# uC.net
KiCad netlist of a schematic drawn in Altium Designer
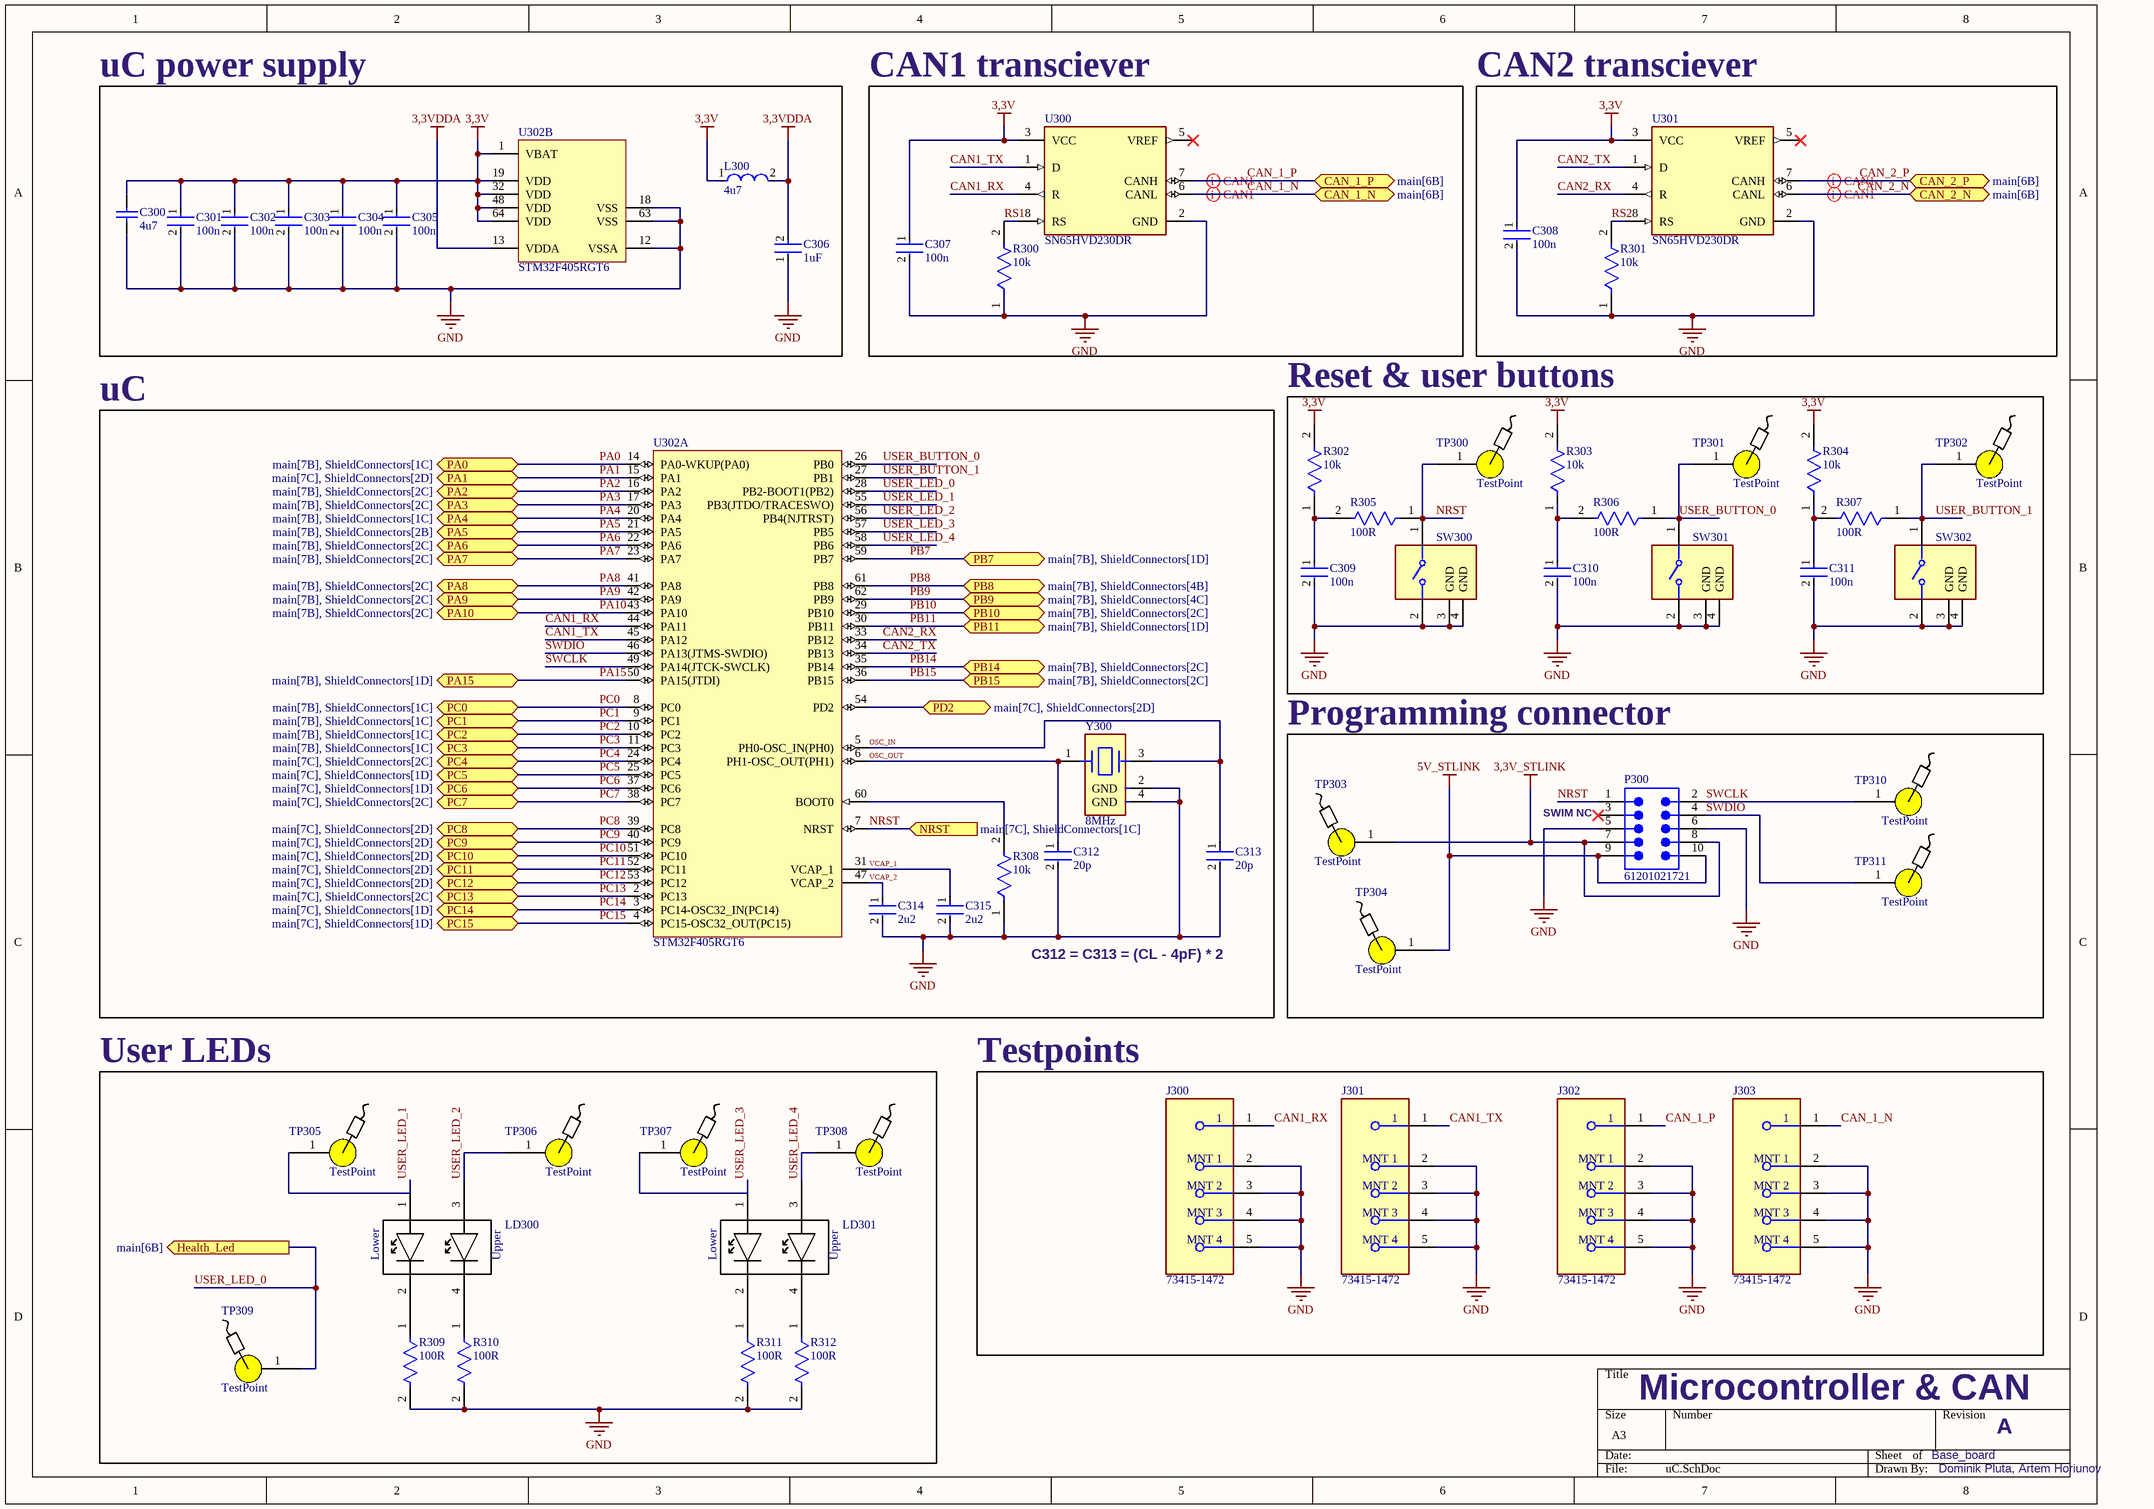
[diagram p0: uC.SchDoc]

(export (version "E")
  (design (tool "Eeschema 10.0.6"))
  (components
    (comp (ref "C300")
      (value "4u7")
      (footprint "CAPC1608X87X35NL15T15")
      (fields (field (name "PART NUMBER") "C0603C475K8PACTU") (field (name "MANUFACTURER") "Kemet"))
      (libsource (lib "Altium Content Vault") (part "CAP"))
    )
    (comp (ref "C301")
      (value "100n")
      (footprint "FP-C0603C-CF-MFG")
      (description "CAP CER 0.1UF 50V X7R 0603")
      (fields (field (name "TOLERANCE") "0.1") (field (name "MANUFACTURER") "KEMET"))
      (libsource (lib "Altium Content Vault") (part "b4654b650e69147ec39a6b967a45e02"))
    )
    (comp (ref "C302")
      (value "100n")
      (footprint "FP-C0603C-CF-MFG")
      (description "CAP CER 0.1UF 50V X7R 0603")
      (fields (field (name "TOLERANCE") "0.1") (field (name "MANUFACTURER") "KEMET"))
      (libsource (lib "Altium Content Vault") (part "b4654b650e69147ec39a6b967a45e02"))
    )
    (comp (ref "C303")
      (value "100n")
      (footprint "FP-C0603C-CF-MFG")
      (description "CAP CER 0.1UF 50V X7R 0603")
      (fields (field (name "TOLERANCE") "0.1") (field (name "MANUFACTURER") "KEMET"))
      (libsource (lib "Altium Content Vault") (part "b4654b650e69147ec39a6b967a45e02"))
    )
    (comp (ref "C304")
      (value "100n")
      (footprint "FP-C0603C-CF-MFG")
      (description "CAP CER 0.1UF 50V X7R 0603")
      (fields (field (name "TOLERANCE") "0.1") (field (name "MANUFACTURER") "KEMET"))
      (libsource (lib "Altium Content Vault") (part "b4654b650e69147ec39a6b967a45e02"))
    )
    (comp (ref "C305")
      (value "100n")
      (footprint "FP-C0603C-CF-MFG")
      (description "CAP CER 0.1UF 50V X7R 0603")
      (fields (field (name "TOLERANCE") "0.1") (field (name "MANUFACTURER") "KEMET"))
      (libsource (lib "Altium Content Vault") (part "b4654b650e69147ec39a6b967a45e02"))
    )
    (comp (ref "C306")
      (value "1uF")
      (footprint "FP-C1608-080-0_1-IPC_B")
      (description "Multilayer Ceramic Capacitors 1μF ±10% 50V X5R SMD 0603")
      (fields (field (name "VOLTAGE") "50V") (field (name "TOLERANCE") "10%"))
      (libsource (lib "Altium Content Vault") (part "236180d848d6139a670b325ea6854c9"))
    )
    (comp (ref "C307")
      (value "100n")
      (footprint "FP-C0603C-CF-MFG")
      (description "CAP CER 0.1UF 50V X7R 0603")
      (fields (field (name "TOLERANCE") "0.1") (field (name "MANUFACTURER") "KEMET"))
      (libsource (lib "Altium Content Vault") (part "b4654b650e69147ec39a6b967a45e02"))
    )
    (comp (ref "C308")
      (value "100n")
      (footprint "FP-C0603C-CF-MFG")
      (description "CAP CER 0.1UF 50V X7R 0603")
      (fields (field (name "TOLERANCE") "0.1") (field (name "MANUFACTURER") "KEMET"))
      (libsource (lib "Altium Content Vault") (part "b4654b650e69147ec39a6b967a45e02"))
    )
    (comp (ref "C309")
      (value "100n")
      (footprint "FP-C0603C-CF-MFG")
      (description "CAP CER 0.1UF 50V X7R 0603")
      (fields (field (name "TOLERANCE") "0.1") (field (name "MANUFACTURER") "KEMET"))
      (libsource (lib "Altium Content Vault") (part "b4654b650e69147ec39a6b967a45e02"))
    )
    (comp (ref "C310")
      (value "100n")
      (footprint "FP-C0603C-CF-MFG")
      (description "CAP CER 0.1UF 50V X7R 0603")
      (fields (field (name "TOLERANCE") "0.1") (field (name "MANUFACTURER") "KEMET"))
      (libsource (lib "Altium Content Vault") (part "b4654b650e69147ec39a6b967a45e02"))
    )
    (comp (ref "C311")
      (value "100n")
      (footprint "FP-C0603C-CF-MFG")
      (description "CAP CER 0.1UF 50V X7R 0603")
      (fields (field (name "TOLERANCE") "0.1") (field (name "MANUFACTURER") "KEMET"))
      (libsource (lib "Altium Content Vault") (part "b4654b650e69147ec39a6b967a45e02"))
    )
    (comp (ref "C312")
      (value "20p")
      (footprint "FP-C0603C-CF-MFG")
      (description "CAP CER 20PF 50V 5% NP0 0603")
      (fields
        (field (name "MANUFACTURER PART NUMBER") "C0603C200J5GACTU")
        (field (name "MANUFACTURER") "KEMET")
      )
      (libsource (lib "Altium Content Vault") (part "b4654b650e69147ec39a6b967a45e02"))
    )
    (comp (ref "C313")
      (value "20p")
      (footprint "FP-C0603C-CF-MFG")
      (description "CAP CER 20PF 50V 5% NP0 0603")
      (fields
        (field (name "MANUFACTURER PART NUMBER") "C0603C200J5GACTU")
        (field (name "MANUFACTURER") "KEMET")
      )
      (libsource (lib "Altium Content Vault") (part "b4654b650e69147ec39a6b967a45e02"))
    )
    (comp (ref "C314")
      (value "2u2")
      (footprint "FP-GRM188-0_1-e0_2_0_5-MFG")
      (description "Chip Multilayer Ceramic Capacitors for General Purpose, 0603, 2.2uF, X7R, 15%, 10%, 10V")
      (fields (field (name "VOLTAGE") "10V") (field (name "TOLERANCE") "10%"))
      (libsource (lib "Altium Content Vault") (part "11868f565c42a9108669ba33697ecf6"))
    )
    (comp (ref "C315")
      (value "2u2")
      (footprint "FP-GRM188-0_1-e0_2_0_5-MFG")
      (description "Chip Multilayer Ceramic Capacitors for General Purpose, 0603, 2.2uF, X7R, 15%, 10%, 10V")
      (fields (field (name "VOLTAGE") "10V") (field (name "TOLERANCE") "10%"))
      (libsource (lib "Altium Content Vault") (part "11868f565c42a9108669ba33697ecf6"))
    )
    (comp (ref "J300")
      (value "73415-1472")
      (footprint "FP-73415-1472-MFG")
      (libsource (lib "Altium Content Vault") (part "c65b8a639cdaef1819ea20b5466f8fa"))
    )
    (comp (ref "J301")
      (value "73415-1472")
      (footprint "FP-73415-1472-MFG")
      (libsource (lib "Altium Content Vault") (part "c65b8a639cdaef1819ea20b5466f8fa"))
    )
    (comp (ref "J302")
      (value "73415-1472")
      (footprint "FP-73415-1472-MFG")
      (libsource (lib "Altium Content Vault") (part "c65b8a639cdaef1819ea20b5466f8fa"))
    )
    (comp (ref "J303")
      (value "73415-1472")
      (footprint "FP-73415-1472-MFG")
      (libsource (lib "Altium Content Vault") (part "c65b8a639cdaef1819ea20b5466f8fa"))
    )
    (comp (ref "L300")
      (value "4u7")
      (footprint "FP-LQM21DH_70-IPC_C")
      (description "Multilayer Type Inductor for General Circuits, 0805 (2012), 22μH, 30%, 0.65Ω, 13mA")
      (fields (field (name "TOLERANCE") "10%"))
      (libsource (lib "Altium Content Vault") (part "725321dda6339637d4d059423bc1c3c"))
    )
    (comp (ref "LD300")
      (value "~")
      (footprint "LedHolder:LED_HOLDER")
      (libsource (lib "LedHolder") (part "DoubleStack_Side_Led_3mm"))
    )
    (comp (ref "LD301")
      (value "~")
      (footprint "LedHolder:LED_HOLDER")
      (libsource (lib "LedHolder") (part "DoubleStack_Side_Led_3mm"))
    )
    (comp (ref "P300")
      (value "61201021721")
      (footprint "61201021721")
      (libsource (lib "Altium Content Vault") (part "Header_Male_2R_10P"))
    )
    (comp (ref "R300")
      (value "10k")
      (footprint "FP-RC0603-0_55-IPC_C")
      (description "RES 10K OHM 1% 1/10W 0603")
      (fields (field (name "TOLERANCE") "1%"))
      (libsource (lib "Altium Content Vault") (part "1029c3af85768c4190bb7ad29bc67b5"))
    )
    (comp (ref "R301")
      (value "10k")
      (footprint "FP-RC0603-0_55-IPC_C")
      (description "RES 10K OHM 1% 1/10W 0603")
      (fields (field (name "TOLERANCE") "1%"))
      (libsource (lib "Altium Content Vault") (part "1029c3af85768c4190bb7ad29bc67b5"))
    )
    (comp (ref "R302")
      (value "10k")
      (footprint "FP-RC0603-0_55-IPC_C")
      (description "RES 10K OHM 1% 1/10W 0603")
      (fields (field (name "TOLERANCE") "1%"))
      (libsource (lib "Altium Content Vault") (part "1029c3af85768c4190bb7ad29bc67b5"))
    )
    (comp (ref "R303")
      (value "10k")
      (footprint "FP-RC0603-0_55-IPC_C")
      (description "RES 10K OHM 1% 1/10W 0603")
      (fields (field (name "TOLERANCE") "1%"))
      (libsource (lib "Altium Content Vault") (part "1029c3af85768c4190bb7ad29bc67b5"))
    )
    (comp (ref "R304")
      (value "10k")
      (footprint "FP-RC0603-0_55-IPC_C")
      (description "RES 10K OHM 1% 1/10W 0603")
      (fields (field (name "TOLERANCE") "1%"))
      (libsource (lib "Altium Content Vault") (part "1029c3af85768c4190bb7ad29bc67b5"))
    )
    (comp (ref "R305")
      (value "100R")
      (footprint "FP-RC0603-0_55-MFG")
      (fields (field (name "TOLERANCE") "1%"))
      (libsource (lib "Altium Content Vault") (part "1029c3af85768c4190bb7ad29bc67b5"))
    )
    (comp (ref "R306")
      (value "100R")
      (footprint "FP-RC0603-0_55-MFG")
      (fields (field (name "TOLERANCE") "1%"))
      (libsource (lib "Altium Content Vault") (part "1029c3af85768c4190bb7ad29bc67b5"))
    )
    (comp (ref "R307")
      (value "100R")
      (footprint "FP-RC0603-0_55-MFG")
      (fields (field (name "TOLERANCE") "1%"))
      (libsource (lib "Altium Content Vault") (part "1029c3af85768c4190bb7ad29bc67b5"))
    )
    (comp (ref "R308")
      (value "10k")
      (footprint "FP-RC0603-0_55-IPC_C")
      (description "RES 10K OHM 1% 1/10W 0603")
      (fields (field (name "TOLERANCE") "1%"))
      (libsource (lib "Altium Content Vault") (part "1029c3af85768c4190bb7ad29bc67b5"))
    )
    (comp (ref "R309")
      (value "100R")
      (footprint "FP-RC0603-0_55-MFG")
      (fields (field (name "TOLERANCE") "1%"))
      (libsource (lib "Altium Content Vault") (part "1029c3af85768c4190bb7ad29bc67b5"))
    )
    (comp (ref "R310")
      (value "100R")
      (footprint "FP-RC0603-0_55-MFG")
      (fields (field (name "TOLERANCE") "1%"))
      (libsource (lib "Altium Content Vault") (part "1029c3af85768c4190bb7ad29bc67b5"))
    )
    (comp (ref "R311")
      (value "100R")
      (footprint "FP-RC0603-0_55-MFG")
      (fields (field (name "TOLERANCE") "1%"))
      (libsource (lib "Altium Content Vault") (part "1029c3af85768c4190bb7ad29bc67b5"))
    )
    (comp (ref "R312")
      (value "100R")
      (footprint "FP-RC0603-0_55-MFG")
      (fields (field (name "TOLERANCE") "1%"))
      (libsource (lib "Altium Content Vault") (part "1029c3af85768c4190bb7ad29bc67b5"))
    )
    (comp (ref "SW300")
      (value "B3F-3122")
      (footprint "FP-B3F-3122-MFG")
      (description "SWITCH TACTILE SPST-NO 0.05A 24V")
      (libsource (lib "Altium Content Vault") (part "05c531d4b500f7e9514fa3f65f375ae"))
    )
    (comp (ref "SW301")
      (value "B3F-3122")
      (footprint "FP-B3F-3122-MFG")
      (description "SWITCH TACTILE SPST-NO 0.05A 24V")
      (libsource (lib "Altium Content Vault") (part "05c531d4b500f7e9514fa3f65f375ae"))
    )
    (comp (ref "SW302")
      (value "B3F-3122")
      (footprint "FP-B3F-3122-MFG")
      (description "SWITCH TACTILE SPST-NO 0.05A 24V")
      (libsource (lib "Altium Content Vault") (part "05c531d4b500f7e9514fa3f65f375ae"))
    )
    (comp (ref "TP300")
      (value "TestPoint")
      (footprint "TestPoint")
      (libsource (lib "TestPoint") (part "TestPoint"))
    )
    (comp (ref "TP301")
      (value "TestPoint")
      (footprint "TestPoint")
      (libsource (lib "TestPoint") (part "TestPoint"))
    )
    (comp (ref "TP302")
      (value "TestPoint")
      (footprint "TestPoint")
      (libsource (lib "TestPoint") (part "TestPoint"))
    )
    (comp (ref "TP303")
      (value "TestPoint")
      (footprint "TestPoint")
      (libsource (lib "TestPoint") (part "TestPoint"))
    )
    (comp (ref "TP304")
      (value "TestPoint")
      (footprint "TestPoint")
      (libsource (lib "TestPoint") (part "TestPoint"))
    )
    (comp (ref "TP305")
      (value "TestPoint")
      (footprint "TestPoint")
      (libsource (lib "TestPoint") (part "TestPoint"))
    )
    (comp (ref "TP306")
      (value "TestPoint")
      (footprint "TestPoint")
      (libsource (lib "TestPoint") (part "TestPoint"))
    )
    (comp (ref "TP307")
      (value "TestPoint")
      (footprint "TestPoint")
      (libsource (lib "TestPoint") (part "TestPoint"))
    )
    (comp (ref "TP308")
      (value "TestPoint")
      (footprint "TestPoint")
      (libsource (lib "TestPoint") (part "TestPoint"))
    )
    (comp (ref "TP309")
      (value "TestPoint")
      (footprint "TestPoint")
      (libsource (lib "TestPoint") (part "TestPoint"))
    )
    (comp (ref "TP310")
      (value "TestPoint")
      (footprint "TestPoint")
      (libsource (lib "TestPoint") (part "TestPoint"))
    )
    (comp (ref "TP311")
      (value "TestPoint")
      (footprint "TestPoint")
      (libsource (lib "TestPoint") (part "TestPoint"))
    )
    (comp (ref "U300")
      (value "SN65HVD230DR")
      (footprint "FP-D0008A-IPC_A")
      (description "IC TRANSCEIVER HALF 1/1 8SOIC")
      (libsource (lib "Altium Content Vault") (part "43b56812b1adf0e60a7acfb7c27ab91"))
    )
    (comp (ref "U301")
      (value "SN65HVD230DR")
      (footprint "FP-D0008A-IPC_A")
      (description "IC TRANSCEIVER HALF 1/1 8SOIC")
      (libsource (lib "Altium Content Vault") (part "43b56812b1adf0e60a7acfb7c27ab91"))
    )
    (comp (ref "U302")
      (value "STM32F405RGT6")
      (footprint "STM-LQFP64_M")
      (fields (field (name "MANUFACTURER") "STMicroelectronics"))
      (libsource (lib "Altium Content Vault") (part "MC-ARM-STM32F4X5-SQ64"))
    )
    (comp (ref "Y300")
      (value "8MHz")
      (footprint "FP-7M-MFG")
      (description "Crystal")
      (fields (field (name "TOLERANCE") "10ppm"))
      (libsource (lib "Altium Content Vault") (part "41079aabb0e87794b56622915be14ed"))
    )
  )
  (nets
    (net (code "2") (name "/CAN1_RX") (class "Default")
      (node (ref "J300") (pin "1") (pinfunction "1_1") (pintype "passive"))
      (node (ref "U300") (pin "4") (pinfunction "R_4") (pintype "output"))
      (node (ref "U302") (pin "44") (pinfunction "PA11_44") (pintype "bidirectional"))
    )
    (net (code "3") (name "/CAN1_TX") (class "Default")
      (node (ref "J301") (pin "1") (pinfunction "1_1") (pintype "passive"))
      (node (ref "U300") (pin "1") (pinfunction "D_1") (pintype "input"))
      (node (ref "U302") (pin "45") (pinfunction "PA12_45") (pintype "bidirectional"))
    )
    (net (code "4") (name "/CAN2_RX") (class "Default")
      (node (ref "U301") (pin "4") (pinfunction "R_4") (pintype "output"))
      (node (ref "U302") (pin "33") (pinfunction "PB12_33") (pintype "bidirectional"))
    )
    (net (code "5") (name "/CAN2_TX") (class "Default")
      (node (ref "U301") (pin "1") (pinfunction "D_1") (pintype "input"))
      (node (ref "U302") (pin "34") (pinfunction "PB13_34") (pintype "bidirectional"))
    )
    (net (code "6") (name "/CAN_1_N") (class "Default")
      (node (ref "J303") (pin "1") (pinfunction "1_1") (pintype "passive"))
      (node (ref "U300") (pin "6") (pinfunction "CANL_6") (pintype "bidirectional"))
    )
    (net (code "7") (name "/CAN_1_P") (class "Default")
      (node (ref "J302") (pin "1") (pinfunction "1_1") (pintype "passive"))
      (node (ref "U300") (pin "7") (pinfunction "CANH_7") (pintype "bidirectional"))
    )
    (net (code "8") (name "/CAN_2_N") (class "Default")
      (node (ref "U301") (pin "6") (pinfunction "CANL_6") (pintype "bidirectional"))
    )
    (net (code "9") (name "/CAN_2_P") (class "Default")
      (node (ref "U301") (pin "7") (pinfunction "CANH_7") (pintype "bidirectional"))
    )
    (net (code "10") (name "/NRST") (class "Default")
      (node (ref "P300") (pin "1") (pinfunction "1_1") (pintype "passive"))
      (node (ref "R305") (pin "1") (pinfunction "1_1") (pintype "passive"))
      (node (ref "SW300") (pin "1") (pinfunction "1_1") (pintype "passive"))
      (node (ref "TP300") (pin "1") (pintype "passive"))
      (node (ref "U302") (pin "7") (pinfunction "NRST_7") (pintype "bidirectional"))
    )
    (net (code "11") (name "/OSC_IN") (class "Default")
      (node (ref "C313") (pin "1") (pinfunction "1_1") (pintype "passive"))
      (node (ref "U302") (pin "5") (pinfunction "PH0-OSC_IN(PH0)_5") (pintype "bidirectional"))
      (node (ref "Y300") (pin "3") (pinfunction "3_3") (pintype "passive"))
    )
    (net (code "12") (name "/OSC_OUT") (class "Default")
      (node (ref "C312") (pin "1") (pinfunction "1_1") (pintype "passive"))
      (node (ref "U302") (pin "6") (pinfunction "PH1-OSC_OUT(PH1)_6") (pintype "bidirectional"))
      (node (ref "Y300") (pin "1") (pinfunction "1_1") (pintype "passive"))
    )
    (net (code "13") (name "/PA0") (class "Default")
      (node (ref "U302") (pin "14") (pinfunction "PA0-WKUP(PA0)_14") (pintype "bidirectional"))
    )
    (net (code "14") (name "/PA1") (class "Default")
      (node (ref "U302") (pin "15") (pinfunction "PA1_15") (pintype "bidirectional"))
    )
    (net (code "15") (name "/PA2") (class "Default")
      (node (ref "U302") (pin "16") (pinfunction "PA2_16") (pintype "bidirectional"))
    )
    (net (code "16") (name "/PA3") (class "Default")
      (node (ref "U302") (pin "17") (pinfunction "PA3_17") (pintype "bidirectional"))
    )
    (net (code "17") (name "/PA4") (class "Default")
      (node (ref "U302") (pin "20") (pinfunction "PA4_20") (pintype "bidirectional"))
    )
    (net (code "18") (name "/PA5") (class "Default")
      (node (ref "U302") (pin "21") (pinfunction "PA5_21") (pintype "bidirectional"))
    )
    (net (code "19") (name "/PA6") (class "Default")
      (node (ref "U302") (pin "22") (pinfunction "PA6_22") (pintype "bidirectional"))
    )
    (net (code "20") (name "/PA7") (class "Default")
      (node (ref "U302") (pin "23") (pinfunction "PA7_23") (pintype "bidirectional"))
    )
    (net (code "21") (name "/PA8") (class "Default")
      (node (ref "U302") (pin "41") (pinfunction "PA8_41") (pintype "bidirectional"))
    )
    (net (code "22") (name "/PA9") (class "Default")
      (node (ref "U302") (pin "42") (pinfunction "PA9_42") (pintype "bidirectional"))
    )
    (net (code "23") (name "/PA10") (class "Default")
      (node (ref "U302") (pin "43") (pinfunction "PA10_43") (pintype "bidirectional"))
    )
    (net (code "24") (name "/PA15") (class "Default")
      (node (ref "U302") (pin "50") (pinfunction "PA15(JTDI)_50") (pintype "bidirectional"))
    )
    (net (code "25") (name "/PB7") (class "Default")
      (node (ref "U302") (pin "59") (pinfunction "PB7_59") (pintype "bidirectional"))
    )
    (net (code "26") (name "/PB8") (class "Default")
      (node (ref "U302") (pin "61") (pinfunction "PB8_61") (pintype "bidirectional"))
    )
    (net (code "27") (name "/PB9") (class "Default")
      (node (ref "U302") (pin "62") (pinfunction "PB9_62") (pintype "bidirectional"))
    )
    (net (code "28") (name "/PB10") (class "Default")
      (node (ref "U302") (pin "29") (pinfunction "PB10_29") (pintype "bidirectional"))
    )
    (net (code "29") (name "/PB11") (class "Default")
      (node (ref "U302") (pin "30") (pinfunction "PB11_30") (pintype "bidirectional"))
    )
    (net (code "30") (name "/PB14") (class "Default")
      (node (ref "U302") (pin "35") (pinfunction "PB14_35") (pintype "bidirectional"))
    )
    (net (code "31") (name "/PB15") (class "Default")
      (node (ref "U302") (pin "36") (pinfunction "PB15_36") (pintype "bidirectional"))
    )
    (net (code "32") (name "/PC0") (class "Default")
      (node (ref "U302") (pin "8") (pinfunction "PC0_8") (pintype "bidirectional"))
    )
    (net (code "33") (name "/PC1") (class "Default")
      (node (ref "U302") (pin "9") (pinfunction "PC1_9") (pintype "bidirectional"))
    )
    (net (code "34") (name "/PC2") (class "Default")
      (node (ref "U302") (pin "10") (pinfunction "PC2_10") (pintype "bidirectional"))
    )
    (net (code "35") (name "/PC3") (class "Default")
      (node (ref "U302") (pin "11") (pinfunction "PC3_11") (pintype "bidirectional"))
    )
    (net (code "36") (name "/PC4") (class "Default")
      (node (ref "U302") (pin "24") (pinfunction "PC4_24") (pintype "bidirectional"))
    )
    (net (code "37") (name "/PC5") (class "Default")
      (node (ref "U302") (pin "25") (pinfunction "PC5_25") (pintype "bidirectional"))
    )
    (net (code "38") (name "/PC6") (class "Default")
      (node (ref "U302") (pin "37") (pinfunction "PC6_37") (pintype "bidirectional"))
    )
    (net (code "39") (name "/PC7") (class "Default")
      (node (ref "U302") (pin "38") (pinfunction "PC7_38") (pintype "bidirectional"))
    )
    (net (code "40") (name "/PC8") (class "Default")
      (node (ref "U302") (pin "39") (pinfunction "PC8_39") (pintype "bidirectional"))
    )
    (net (code "41") (name "/PC9") (class "Default")
      (node (ref "U302") (pin "40") (pinfunction "PC9_40") (pintype "bidirectional"))
    )
    (net (code "42") (name "/PC10") (class "Default")
      (node (ref "U302") (pin "51") (pinfunction "PC10_51") (pintype "bidirectional"))
    )
    (net (code "43") (name "/PC11") (class "Default")
      (node (ref "U302") (pin "52") (pinfunction "PC11_52") (pintype "bidirectional"))
    )
    (net (code "44") (name "/PC12") (class "Default")
      (node (ref "U302") (pin "53") (pinfunction "PC12_53") (pintype "bidirectional"))
    )
    (net (code "45") (name "/PC13") (class "Default")
      (node (ref "U302") (pin "2") (pinfunction "PC13_2") (pintype "bidirectional"))
    )
    (net (code "46") (name "/PC14") (class "Default")
      (node (ref "U302") (pin "3") (pinfunction "PC14-OSC32_IN(PC14)_3") (pintype "bidirectional"))
    )
    (net (code "47") (name "/PC15") (class "Default")
      (node (ref "U302") (pin "4") (pinfunction "PC15-OSC32_OUT(PC15)_4") (pintype "bidirectional"))
    )
    (net (code "48") (name "/PD2") (class "Default")
      (node (ref "U302") (pin "54") (pinfunction "PD2_54") (pintype "bidirectional"))
    )
    (net (code "49") (name "/RS1") (class "Default")
      (node (ref "R300") (pin "2") (pinfunction "2_2") (pintype "passive"))
      (node (ref "U300") (pin "8") (pinfunction "RS_8") (pintype "input"))
    )
    (net (code "50") (name "/RS2") (class "Default")
      (node (ref "R301") (pin "2") (pinfunction "2_2") (pintype "passive"))
      (node (ref "U301") (pin "8") (pinfunction "RS_8") (pintype "input"))
    )
    (net (code "51") (name "/SWCLK") (class "Default")
      (node (ref "P300") (pin "2") (pinfunction "2_2") (pintype "passive"))
      (node (ref "TP310") (pin "1") (pintype "passive"))
      (node (ref "U302") (pin "49") (pinfunction "PA14(JTCK-SWCLK)_49") (pintype "bidirectional"))
    )
    (net (code "52") (name "/SWDIO") (class "Default")
      (node (ref "P300") (pin "4") (pinfunction "4_4") (pintype "passive"))
      (node (ref "TP311") (pin "1") (pintype "passive"))
      (node (ref "U302") (pin "46") (pinfunction "PA13(JTMS-SWDIO)_46") (pintype "bidirectional"))
    )
    (net (code "53") (name "/USER_BUTTON_0") (class "Default")
      (node (ref "R306") (pin "1") (pinfunction "1_1") (pintype "passive"))
      (node (ref "SW301") (pin "1") (pinfunction "1_1") (pintype "passive"))
      (node (ref "TP301") (pin "1") (pintype "passive"))
      (node (ref "U302") (pin "26") (pinfunction "PB0_26") (pintype "bidirectional"))
    )
    (net (code "54") (name "/USER_BUTTON_1") (class "Default")
      (node (ref "R307") (pin "1") (pinfunction "1_1") (pintype "passive"))
      (node (ref "SW302") (pin "1") (pinfunction "1_1") (pintype "passive"))
      (node (ref "TP302") (pin "1") (pintype "passive"))
      (node (ref "U302") (pin "27") (pinfunction "PB1_27") (pintype "bidirectional"))
    )
    (net (code "55") (name "/USER_LED_0") (class "Default")
      (node (ref "TP309") (pin "1") (pintype "passive"))
      (node (ref "U302") (pin "28") (pinfunction "PB2-BOOT1(PB2)_28") (pintype "bidirectional"))
    )
    (net (code "56") (name "/USER_LED_1") (class "Default")
      (node (ref "LD300") (pin "1") (pintype "passive"))
      (node (ref "TP305") (pin "1") (pintype "passive"))
      (node (ref "U302") (pin "55") (pinfunction "PB3(JTDO/TRACESWO)_55") (pintype "bidirectional"))
    )
    (net (code "57") (name "/USER_LED_2") (class "Default")
      (node (ref "LD300") (pin "3") (pintype "passive"))
      (node (ref "TP306") (pin "1") (pintype "passive"))
      (node (ref "U302") (pin "56") (pinfunction "PB4(NJTRST)_56") (pintype "bidirectional"))
    )
    (net (code "58") (name "/USER_LED_3") (class "Default")
      (node (ref "LD301") (pin "1") (pintype "passive"))
      (node (ref "TP307") (pin "1") (pintype "passive"))
      (node (ref "U302") (pin "57") (pinfunction "PB5_57") (pintype "bidirectional"))
    )
    (net (code "59") (name "/USER_LED_4") (class "Default")
      (node (ref "LD301") (pin "3") (pintype "passive"))
      (node (ref "TP308") (pin "1") (pintype "passive"))
      (node (ref "U302") (pin "58") (pinfunction "PB6_58") (pintype "bidirectional"))
    )
    (net (code "60") (name "/VCAP_1") (class "Default")
      (node (ref "C315") (pin "1") (pinfunction "1_1") (pintype "passive"))
      (node (ref "U302") (pin "31") (pinfunction "VCAP_1_31") (pintype "power_in"))
    )
    (net (code "61") (name "/VCAP_2") (class "Default")
      (node (ref "C314") (pin "1") (pinfunction "1_1") (pintype "passive"))
      (node (ref "U302") (pin "47") (pinfunction "VCAP_2_47") (pintype "power_in"))
    )
    (net (code "62") (name "3,3V") (class "Default")
      (node (ref "C300") (pin "2") (pinfunction "2_2") (pintype "passive"))
      (node (ref "C301") (pin "1") (pinfunction "1_1") (pintype "passive"))
      (node (ref "C302") (pin "1") (pinfunction "1_1") (pintype "passive"))
      (node (ref "C303") (pin "1") (pinfunction "1_1") (pintype "passive"))
      (node (ref "C304") (pin "1") (pinfunction "1_1") (pintype "passive"))
      (node (ref "C305") (pin "1") (pinfunction "1_1") (pintype "passive"))
      (node (ref "C307") (pin "1") (pinfunction "1_1") (pintype "passive"))
      (node (ref "C308") (pin "1") (pinfunction "1_1") (pintype "passive"))
      (node (ref "L300") (pin "1") (pinfunction "1_1") (pintype "passive"))
      (node (ref "R302") (pin "2") (pinfunction "2_2") (pintype "passive"))
      (node (ref "R303") (pin "2") (pinfunction "2_2") (pintype "passive"))
      (node (ref "R304") (pin "2") (pinfunction "2_2") (pintype "passive"))
      (node (ref "U300") (pin "3") (pinfunction "VCC_3") (pintype "power_in"))
      (node (ref "U301") (pin "3") (pinfunction "VCC_3") (pintype "power_in"))
      (node (ref "U302") (pin "1") (pinfunction "VBAT_1") (pintype "power_in"))
      (node (ref "U302") (pin "19") (pinfunction "VDD_19") (pintype "power_in"))
      (node (ref "U302") (pin "32") (pinfunction "VDD_32") (pintype "power_in"))
      (node (ref "U302") (pin "48") (pinfunction "VDD_48") (pintype "power_in"))
      (node (ref "U302") (pin "64") (pinfunction "VDD_64") (pintype "power_in"))
    )
    (net (code "63") (name "3,3VDDA") (class "Default")
      (node (ref "C306") (pin "2") (pinfunction "2_2") (pintype "passive"))
      (node (ref "L300") (pin "2") (pinfunction "2_2") (pintype "passive"))
      (node (ref "U302") (pin "13") (pinfunction "VDDA_13") (pintype "power_in"))
    )
    (net (code "64") (name "3,3V_STLINK") (class "Default")
      (node (ref "P300") (pin "7") (pinfunction "7_7") (pintype "passive"))
      (node (ref "P300") (pin "8") (pinfunction "8_8") (pintype "passive"))
      (node (ref "TP303") (pin "1") (pintype "passive"))
    )
    (net (code "65") (name "5V_STLINK") (class "Default")
      (node (ref "P300") (pin "10") (pinfunction "10_10") (pintype "passive"))
      (node (ref "P300") (pin "9") (pinfunction "9_9") (pintype "passive"))
      (node (ref "TP304") (pin "1") (pintype "passive"))
    )
    (net (code "66") (name "GND") (class "Default")
      (node (ref "C300") (pin "1") (pinfunction "1_1") (pintype "passive"))
      (node (ref "C301") (pin "2") (pinfunction "2_2") (pintype "passive"))
      (node (ref "C302") (pin "2") (pinfunction "2_2") (pintype "passive"))
      (node (ref "C303") (pin "2") (pinfunction "2_2") (pintype "passive"))
      (node (ref "C304") (pin "2") (pinfunction "2_2") (pintype "passive"))
      (node (ref "C305") (pin "2") (pinfunction "2_2") (pintype "passive"))
      (node (ref "C306") (pin "1") (pinfunction "1_1") (pintype "passive"))
      (node (ref "C307") (pin "2") (pinfunction "2_2") (pintype "passive"))
      (node (ref "C308") (pin "2") (pinfunction "2_2") (pintype "passive"))
      (node (ref "C309") (pin "2") (pinfunction "2_2") (pintype "passive"))
      (node (ref "C310") (pin "2") (pinfunction "2_2") (pintype "passive"))
      (node (ref "C311") (pin "2") (pinfunction "2_2") (pintype "passive"))
      (node (ref "C312") (pin "2") (pinfunction "2_2") (pintype "passive"))
      (node (ref "C313") (pin "2") (pinfunction "2_2") (pintype "passive"))
      (node (ref "C314") (pin "2") (pinfunction "2_2") (pintype "passive"))
      (node (ref "C315") (pin "2") (pinfunction "2_2") (pintype "passive"))
      (node (ref "J300") (pin "2") (pinfunction "MNT_1_2") (pintype "passive"))
      (node (ref "J300") (pin "3") (pinfunction "MNT_2_3") (pintype "passive"))
      (node (ref "J300") (pin "4") (pinfunction "MNT_3_4") (pintype "passive"))
      (node (ref "J300") (pin "5") (pinfunction "MNT_4_5") (pintype "passive"))
      (node (ref "J301") (pin "2") (pinfunction "MNT_1_2") (pintype "passive"))
      (node (ref "J301") (pin "3") (pinfunction "MNT_2_3") (pintype "passive"))
      (node (ref "J301") (pin "4") (pinfunction "MNT_3_4") (pintype "passive"))
      (node (ref "J301") (pin "5") (pinfunction "MNT_4_5") (pintype "passive"))
      (node (ref "J302") (pin "2") (pinfunction "MNT_1_2") (pintype "passive"))
      (node (ref "J302") (pin "3") (pinfunction "MNT_2_3") (pintype "passive"))
      (node (ref "J302") (pin "4") (pinfunction "MNT_3_4") (pintype "passive"))
      (node (ref "J302") (pin "5") (pinfunction "MNT_4_5") (pintype "passive"))
      (node (ref "J303") (pin "2") (pinfunction "MNT_1_2") (pintype "passive"))
      (node (ref "J303") (pin "3") (pinfunction "MNT_2_3") (pintype "passive"))
      (node (ref "J303") (pin "4") (pinfunction "MNT_3_4") (pintype "passive"))
      (node (ref "J303") (pin "5") (pinfunction "MNT_4_5") (pintype "passive"))
      (node (ref "P300") (pin "5") (pinfunction "5_5") (pintype "passive"))
      (node (ref "P300") (pin "6") (pinfunction "6_6") (pintype "passive"))
      (node (ref "R300") (pin "1") (pinfunction "1_1") (pintype "passive"))
      (node (ref "R301") (pin "1") (pinfunction "1_1") (pintype "passive"))
      (node (ref "R308") (pin "1") (pinfunction "1_1") (pintype "passive"))
      (node (ref "R309") (pin "2") (pinfunction "2_2") (pintype "passive"))
      (node (ref "R310") (pin "2") (pinfunction "2_2") (pintype "passive"))
      (node (ref "R311") (pin "2") (pinfunction "2_2") (pintype "passive"))
      (node (ref "R312") (pin "2") (pinfunction "2_2") (pintype "passive"))
      (node (ref "SW300") (pin "2") (pinfunction "2_2") (pintype "passive"))
      (node (ref "SW300") (pin "3") (pinfunction "GND_3") (pintype "power_in"))
      (node (ref "SW300") (pin "4") (pinfunction "GND_4") (pintype "power_in"))
      (node (ref "SW301") (pin "2") (pinfunction "2_2") (pintype "passive"))
      (node (ref "SW301") (pin "3") (pinfunction "GND_3") (pintype "power_in"))
      (node (ref "SW301") (pin "4") (pinfunction "GND_4") (pintype "power_in"))
      (node (ref "SW302") (pin "2") (pinfunction "2_2") (pintype "passive"))
      (node (ref "SW302") (pin "3") (pinfunction "GND_3") (pintype "power_in"))
      (node (ref "SW302") (pin "4") (pinfunction "GND_4") (pintype "power_in"))
      (node (ref "U300") (pin "2") (pinfunction "GND_2") (pintype "power_in"))
      (node (ref "U301") (pin "2") (pinfunction "GND_2") (pintype "power_in"))
      (node (ref "U302") (pin "12") (pinfunction "VSSA_12") (pintype "power_in"))
      (node (ref "U302") (pin "18") (pinfunction "VSS_18") (pintype "power_in"))
      (node (ref "U302") (pin "63") (pinfunction "VSS_63") (pintype "power_in"))
      (node (ref "Y300") (pin "2") (pinfunction "GND_2") (pintype "power_in"))
      (node (ref "Y300") (pin "4") (pinfunction "GND_4") (pintype "power_in"))
    )
    (net (code "67") (name "Net-(C309-Pad1)") (class "Default")
      (node (ref "C309") (pin "1") (pinfunction "1_1") (pintype "passive"))
      (node (ref "R302") (pin "1") (pinfunction "1_1") (pintype "passive"))
      (node (ref "R305") (pin "2") (pinfunction "2_2") (pintype "passive"))
    )
    (net (code "68") (name "Net-(C310-Pad1)") (class "Default")
      (node (ref "C310") (pin "1") (pinfunction "1_1") (pintype "passive"))
      (node (ref "R303") (pin "1") (pinfunction "1_1") (pintype "passive"))
      (node (ref "R306") (pin "2") (pinfunction "2_2") (pintype "passive"))
    )
    (net (code "69") (name "Net-(C311-Pad1)") (class "Default")
      (node (ref "C311") (pin "1") (pinfunction "1_1") (pintype "passive"))
      (node (ref "R304") (pin "1") (pinfunction "1_1") (pintype "passive"))
      (node (ref "R307") (pin "2") (pinfunction "2_2") (pintype "passive"))
    )
    (net (code "70") (name "Net-(LD300-Pad2)") (class "Default")
      (node (ref "LD300") (pin "2") (pintype "passive"))
      (node (ref "R309") (pin "1") (pinfunction "1_1") (pintype "passive"))
    )
    (net (code "71") (name "Net-(LD300-Pad4)") (class "Default")
      (node (ref "LD300") (pin "4") (pintype "passive"))
      (node (ref "R310") (pin "1") (pinfunction "1_1") (pintype "passive"))
    )
    (net (code "72") (name "Net-(LD301-Pad2)") (class "Default")
      (node (ref "LD301") (pin "2") (pintype "passive"))
      (node (ref "R311") (pin "1") (pinfunction "1_1") (pintype "passive"))
    )
    (net (code "73") (name "Net-(LD301-Pad4)") (class "Default")
      (node (ref "LD301") (pin "4") (pintype "passive"))
      (node (ref "R312") (pin "1") (pinfunction "1_1") (pintype "passive"))
    )
    (net (code "74") (name "Net-(U302A-BOOT0)") (class "Default")
      (node (ref "R308") (pin "2") (pinfunction "2_2") (pintype "passive"))
      (node (ref "U302") (pin "60") (pinfunction "BOOT0_60") (pintype "input"))
    )
    (net (code "75") (name "unconnected-(P300-Pad3)") (class "Default")
      (node (ref "P300") (pin "3") (pinfunction "3_3") (pintype "passive+no_connect"))
    )
    (net (code "76") (name "unconnected-(U300-VREF-Pad5)") (class "Default")
      (node (ref "U300") (pin "5") (pinfunction "VREF_5") (pintype "output+no_connect"))
    )
    (net (code "77") (name "unconnected-(U301-VREF-Pad5)") (class "Default")
      (node (ref "U301") (pin "5") (pinfunction "VREF_5") (pintype "output+no_connect"))
    )
  )
)
